# Main_Sheet_-_Comments.net
KiCad netlist of a schematic drawn in Altium Designer
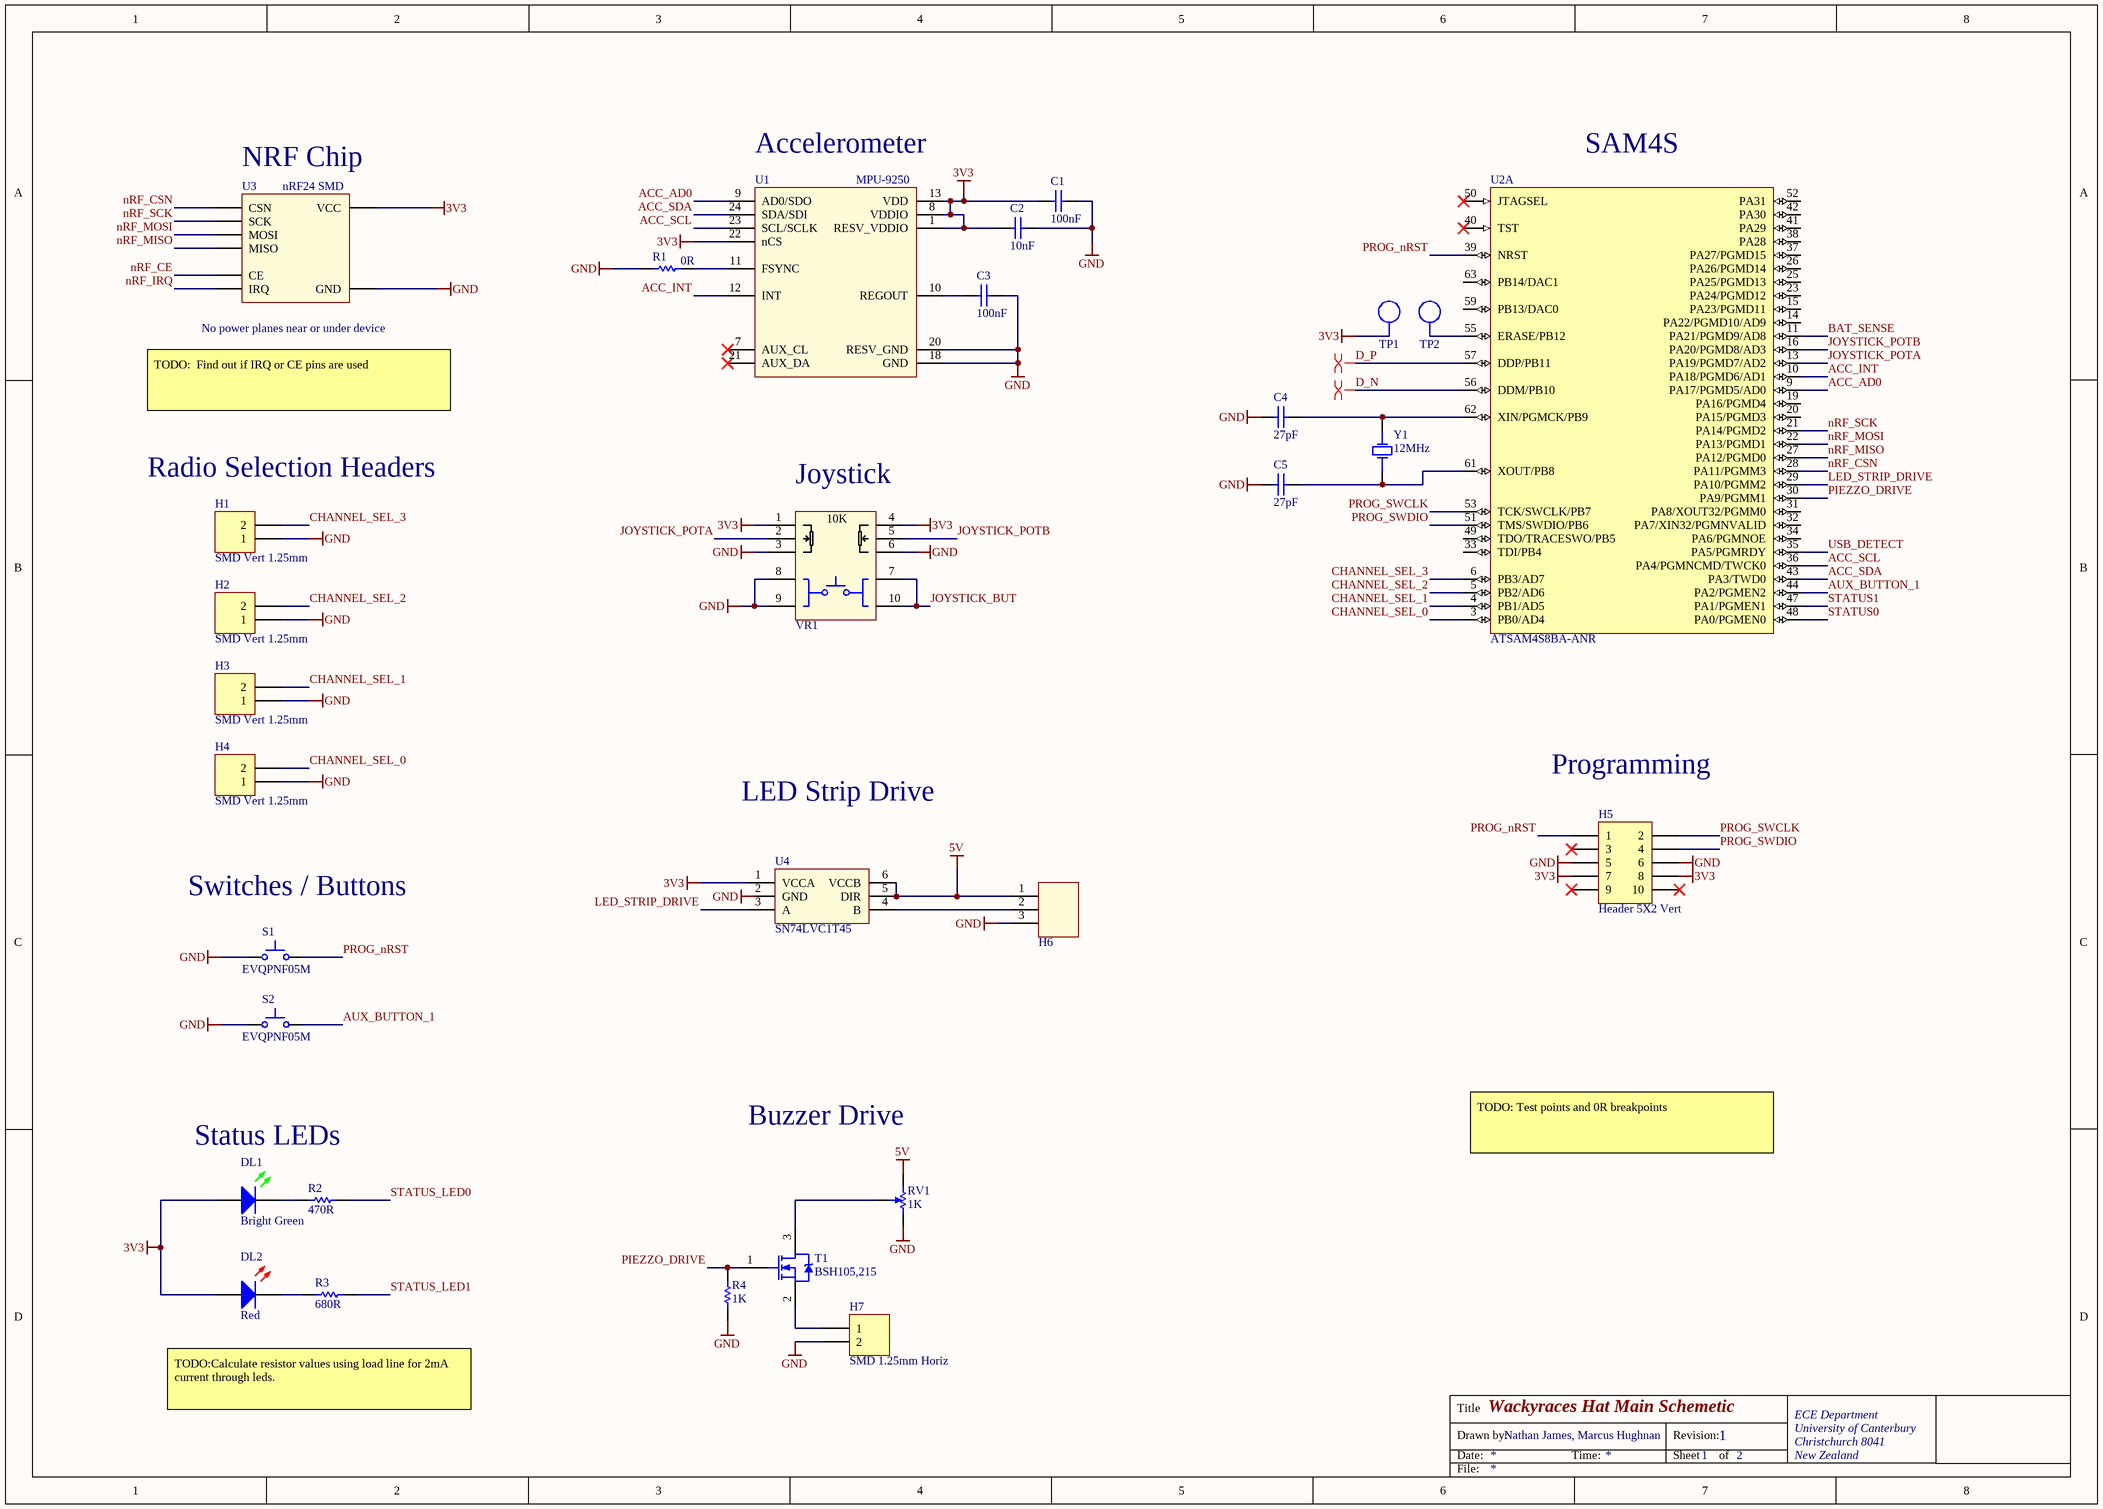
[diagram p0: Main Sheet - Comments.SchDoc]

(export (version "E")
  (design (tool "Eeschema 10.0.6"))
  (components
    (comp (ref "C1")
      (value "100nF")
      (footprint "CAPC1608L")
      (description "CAP CER 100nF X7R +-10% 50V 0603")
      (libsource (lib "ECE AD19Components_19V1") (part "CC_100nF_0603"))
    )
    (comp (ref "C2")
      (value "10nF")
      (footprint "CAPC1608L")
      (description "CAP CER 10nF X7R +-10% 50V 0603")
      (libsource (lib "ECE AD19Components_19V1") (part "CC_10nF_0603"))
    )
    (comp (ref "C3")
      (value "100nF")
      (footprint "CAPC1608L")
      (description "CAP CER 100nF X7R +-10% 50V 0603")
      (libsource (lib "ECE AD19Components_19V1") (part "CC_100nF_0603"))
    )
    (comp (ref "C4")
      (value "27pF")
      (footprint "CAPC1608L")
      (description "CAP CER 27pF NPO/COG +-5% 50V 0603")
      (libsource (lib "ECE AD19Components_19V1") (part "CC_27pF_0603"))
    )
    (comp (ref "C5")
      (value "27pF")
      (footprint "CAPC1608L")
      (description "CAP CER 27pF NPO/COG +-5% 50V 0603")
      (libsource (lib "ECE AD19Components_19V1") (part "CC_27pF_0603"))
    )
    (comp (ref "DL1")
      (value "Bright Green")
      (footprint "WL-SMCW0603")
      (description "LED Bright Green 40mcd 0603 SMD")
      (fields
        (field (name "MANUFACTURER") "WURTH ELEKTRONIK")
        (field (name "MANUFACTURER PART NUMBER") "150060VS75000")
        (field (name "LED COLOUR") "Bright Green")
      )
      (libsource (lib "ECE AD19Components_19V1") (part "DL_150060VS75000"))
    )
    (comp (ref "DL2")
      (value "Red")
      (footprint "WL-SMCW0603")
      (description "LED Red 250mcd 0603 SMD")
      (fields
        (field (name "MANUFACTURER") "WURTH ELEKTRONIK")
        (field (name "MANUFACTURER PART NUMBER") "150060RS75000")
        (field (name "LED COLOUR") "Red")
      )
      (libsource (lib "ECE AD19Components_19V1") (part "DL_150060RS75000"))
    )
    (comp (ref "H1")
      (value "SMD Vert 1.25mm")
      (footprint "SD-53398-0219")
      (description "Header_Vert_2Pos_1.25mm_125V@1A_SMT")
      (fields
        (field (name "MANUFACTURER") "Molex Inc")
        (field (name "MANUFACTURER PART NUMBER") "0533980271")
      )
      (libsource (lib "ECE AD19Components_19V1") (part "JB_53398-02"))
    )
    (comp (ref "H2")
      (value "SMD Vert 1.25mm")
      (footprint "SD-53398-0219")
      (description "Header_Vert_2Pos_1.25mm_125V@1A_SMT")
      (fields
        (field (name "MANUFACTURER") "Molex Inc")
        (field (name "MANUFACTURER PART NUMBER") "0533980271")
      )
      (libsource (lib "ECE AD19Components_19V1") (part "JB_53398-02"))
    )
    (comp (ref "H3")
      (value "SMD Vert 1.25mm")
      (footprint "SD-53398-0219")
      (description "Header_Vert_2Pos_1.25mm_125V@1A_SMT")
      (fields
        (field (name "MANUFACTURER") "Molex Inc")
        (field (name "MANUFACTURER PART NUMBER") "0533980271")
      )
      (libsource (lib "ECE AD19Components_19V1") (part "JB_53398-02"))
    )
    (comp (ref "H4")
      (value "SMD Vert 1.25mm")
      (footprint "SD-53398-0219")
      (description "Header_Vert_2Pos_1.25mm_125V@1A_SMT")
      (fields
        (field (name "MANUFACTURER") "Molex Inc")
        (field (name "MANUFACTURER PART NUMBER") "0533980271")
      )
      (libsource (lib "ECE AD19Components_19V1") (part "JB_53398-02"))
    )
    (comp (ref "H5")
      (value "Header 5X2 Vert")
      (footprint "IDC2.54-V10D")
      (description "IDC Header, 2,54mm, 10-Pin, Vert")
      (libsource (lib "ECE AD19Components_19V1") (part "JA_HDR_IDC_5X2_VERT"))
    )
    (comp (ref "H6")
      (value "HEADER_3")
      (footprint "HEADER_3POS")
      (description "3Pin Header 2.54mm spacing")
      (libsource (lib "ENCE461AD19_19V2") (part "HEADER_3"))
    )
    (comp (ref "H7")
      (value "SMD 1.25mm Horiz")
      (footprint "SD-53261-0219")
      (description "Header_Horiz_2Pos_1.25mm_125V@1A_SMT")
      (fields (field (name "MANUFACTURER") "MOLEX") (field (name "MANUFACTURER PART NUMBER") "53261-0271"))
      (libsource (lib "ECE AD19Components_19V1") (part "JB_53261-02"))
    )
    (comp (ref "R1")
      (value "0R")
      (footprint "RESC1608L")
      (description "RES 0.0 OHM 1/10W 5% 0603 SMD")
      (libsource (lib "ECE AD19Components_19V1") (part "RS_0R0"))
    )
    (comp (ref "R2")
      (value "470R")
      (footprint "RESC1608L")
      (description "RES 470 OHM 1/10W 5% 0603 SMD")
      (libsource (lib "ECE AD19Components_19V1") (part "RS_470R"))
    )
    (comp (ref "R3")
      (value "680R")
      (footprint "RESC3216L")
      (description "RES 680R OHM 1/4W 5% 1206 SMD")
      (libsource (lib "ECE AD19Components_19V1") (part "RT_680R"))
    )
    (comp (ref "R4")
      (value "1K")
      (footprint "RESC1608L")
      (description "RES 1.0K OHM 1/10W 5% 0603 SMD")
      (libsource (lib "ECE AD19Components_19V1") (part "RS_1K"))
    )
    (comp (ref "RV1")
      (value "1K")
      (footprint "PVZ2A")
      (description "Trim Pot SMD 1K Murata PVZ2 Series SMD")
      (fields
        (field (name "MANUFACTURER") "MURATA")
        (field (name "MANUFACTURER PART NUMBER") "PVZ2A102C04B00")
      )
      (libsource (lib "ECE AD19Components_19V1") (part "RM_1K"))
    )
    (comp (ref "S1")
      (value "EVQPNF05M")
      (footprint "EVQPNF05M")
      (description "Panasonic 6 x 3.5mm SMD Light Touch Switch Type SMD")
      (fields (field (name "MANUFACTURER") "Panasonic"))
      (libsource (lib "ECE AD19Components_19V1") (part "WS_EVQPNF05M"))
    )
    (comp (ref "S2")
      (value "EVQPNF05M")
      (footprint "EVQPNF05M")
      (description "Panasonic 6 x 3.5mm SMD Light Touch Switch Type SMD")
      (fields (field (name "MANUFACTURER") "Panasonic"))
      (libsource (lib "ECE AD19Components_19V1") (part "WS_EVQPNF05M"))
    )
    (comp (ref "T1")
      (value "BSH105,215")
      (footprint "SOT23_L")
      (description "MOSFET N-CH 20V 1.05A SOT-23")
      (fields
        (field (name "MANUFACTURER") "NXP Semiconductors")
        (field (name "MANUFACTURER PART NUMBER") "BSH105,215")
      )
      (libsource (lib "ECE AD19Components_19V1") (part "TM_BSH105"))
    )
    (comp (ref "TP1")
      (value "Erase")
      (footprint "TP_1206")
      (description "Test-Point 3.3x1.6x2.1mm SMD")
      (fields
        (field (name "MANUFACTURER") "Harwin Inc")
        (field (name "MANUFACTURER PART NUMBER") "S1751-46R")
      )
      (libsource (lib "ECE AD19Components_19V1") (part "TP_1206"))
    )
    (comp (ref "TP2")
      (value "Erase")
      (footprint "TP_1206")
      (description "Test-Point 3.3x1.6x2.1mm SMD")
      (fields
        (field (name "MANUFACTURER") "Harwin Inc")
        (field (name "MANUFACTURER PART NUMBER") "S1751-46R")
      )
      (libsource (lib "ECE AD19Components_19V1") (part "TP_1206"))
    )
    (comp (ref "U1")
      (value "MPU-9250")
      (footprint "Quad24")
      (description "9 axis IMU")
      (libsource (lib "ENCE461AD19_19V2") (part "MPU-9250"))
    )
    (comp (ref "U2")
      (value "ATSAM4S8BA-ANR")
      (footprint "LQFP64_L")
      (description "IC MCU 32BIT 512KB FLASH 64LQFP")
      (fields (field (name "MANUFACTURER") "Atmel"))
      (libsource (lib "ECE AD19Components_19V1") (part "SE_ATSAM4S16BA-MU"))
    )
    (comp (ref "U3")
      (value "nRF24 SMD")
      (footprint "NRF24")
      (description "nRF24 SMD Module")
      (fields (field (name "WARNING") "No power planes near or under device"))
      (libsource (lib "ENCE461AD19_19V2") (part "NRF24"))
    )
    (comp (ref "U4")
      (value "SN74LVC1T45")
      (footprint "SOT23-6_N")
      (description "1.8V - 5V level converter")
      (libsource (lib "ENCE461_extras_2020") (part "SN74LVC1T45"))
    )
    (comp (ref "VR1")
      (value "Joystick 10k with Sw")
      (footprint "Joystick_Sw")
      (description "JOYSTICK 10K OHM 2 AXIS TH")
      (libsource (lib "ENCE461AD19_19V2") (part "Joystick 10k with Sw"))
    )
    (comp (ref "Y1")
      (value "12MHz")
      (footprint "6.0X3.5-4")
      (description "CRYSTAL 12MHZ 18PF 6X3.5mm SMD")
      (fields
        (field (name "MANUFACTURER") "CTS-Frequency Controls")
        (field (name "MANUFACTURER PART NUMBER") "406C35D12M00000")
        (field (name "FREQUENCY") "12MHz")
      )
      (libsource (lib "ECE AD19Components_19V1") (part "XT_CRYSTAL_12MHz_18pF"))
    )
  )
  (nets
    (net (code "1") (name "/ACC_AD0") (class "Default")
      (node (ref "U1") (pin "9") (pinfunction "AD0/SDO_9") (pintype "passive"))
      (node (ref "U2") (pin "9") (pinfunction "PA17/PGMD5/AD0_9") (pintype "bidirectional"))
    )
    (net (code "2") (name "/ACC_INT") (class "Default")
      (node (ref "U1") (pin "12") (pinfunction "INT_12") (pintype "passive"))
      (node (ref "U2") (pin "10") (pinfunction "PA18/PGMD6/AD1_10") (pintype "bidirectional"))
    )
    (net (code "3") (name "/ACC_SCL") (class "Default")
      (node (ref "U1") (pin "23") (pinfunction "SCL/SCLK_23") (pintype "passive"))
      (node (ref "U2") (pin "36") (pinfunction "PA4/PGMNCMD/TWCK0_36") (pintype "bidirectional"))
    )
    (net (code "4") (name "/ACC_SDA") (class "Default")
      (node (ref "U1") (pin "24") (pinfunction "SDA/SDI_24") (pintype "passive"))
      (node (ref "U2") (pin "43") (pinfunction "PA3/TWD0_43") (pintype "bidirectional"))
    )
    (net (code "5") (name "/AUX_BUTTON_1") (class "Default")
      (node (ref "S2") (pin "2") (pintype "passive"))
      (node (ref "U2") (pin "44") (pinfunction "PA2/PGMEN2_44") (pintype "bidirectional"))
    )
    (net (code "6") (name "/BAT_SENSE") (class "Default")
      (node (ref "U2") (pin "11") (pinfunction "PA21/PGMD9/AD8_11") (pintype "bidirectional"))
    )
    (net (code "7") (name "/CHANNEL_SEL_0") (class "Default")
      (node (ref "H4") (pin "2") (pinfunction "2_2") (pintype "passive"))
      (node (ref "U2") (pin "3") (pinfunction "PB0/AD4_3") (pintype "bidirectional"))
    )
    (net (code "8") (name "/CHANNEL_SEL_1") (class "Default")
      (node (ref "H3") (pin "2") (pinfunction "2_2") (pintype "passive"))
      (node (ref "U2") (pin "4") (pinfunction "PB1/AD5_4") (pintype "bidirectional"))
    )
    (net (code "9") (name "/CHANNEL_SEL_2") (class "Default")
      (node (ref "H2") (pin "2") (pinfunction "2_2") (pintype "passive"))
      (node (ref "U2") (pin "5") (pinfunction "PB2/AD6_5") (pintype "bidirectional"))
    )
    (net (code "10") (name "/CHANNEL_SEL_3") (class "Default")
      (node (ref "H1") (pin "2") (pinfunction "2_2") (pintype "passive"))
      (node (ref "U2") (pin "6") (pinfunction "PB3/AD7_6") (pintype "bidirectional"))
    )
    (net (code "11") (name "/D_N") (class "Default")
      (node (ref "U2") (pin "56") (pinfunction "DDM/PB10_56") (pintype "bidirectional"))
    )
    (net (code "12") (name "/D_P") (class "Default")
      (node (ref "U2") (pin "57") (pinfunction "DDP/PB11_57") (pintype "bidirectional"))
    )
    (net (code "13") (name "/JOYSTICK_BUT") (class "Default")
      (node (ref "VR1") (pin "10") (pinfunction "10_10") (pintype "passive"))
      (node (ref "VR1") (pin "7") (pinfunction "7_7") (pintype "passive"))
    )
    (net (code "14") (name "/JOYSTICK_POTA") (class "Default")
      (node (ref "U2") (pin "13") (pinfunction "PA19/PGMD7/AD2_13") (pintype "bidirectional"))
      (node (ref "VR1") (pin "2") (pinfunction "2_2") (pintype "passive"))
    )
    (net (code "15") (name "/JOYSTICK_POTB") (class "Default")
      (node (ref "U2") (pin "16") (pinfunction "PA20/PGMD8/AD3_16") (pintype "bidirectional"))
      (node (ref "VR1") (pin "5") (pinfunction "2'_5") (pintype "passive"))
    )
    (net (code "16") (name "/LED_STRIP_DRIVE") (class "Default")
      (node (ref "U2") (pin "29") (pinfunction "PA10/PGMM2_29") (pintype "bidirectional"))
      (node (ref "U4") (pin "3") (pinfunction "A_3") (pintype "passive"))
    )
    (net (code "17") (name "/PIEZZO_DRIVE") (class "Default")
      (node (ref "R4") (pin "2") (pinfunction "2_2") (pintype "passive"))
      (node (ref "T1") (pin "1") (pinfunction "1_1") (pintype "passive"))
      (node (ref "U2") (pin "30") (pinfunction "PA9/PGMM1_30") (pintype "bidirectional"))
    )
    (net (code "18") (name "/PROG_SWCLK") (class "Default")
      (node (ref "H5") (pin "2") (pinfunction "2_2") (pintype "passive"))
      (node (ref "U2") (pin "53") (pinfunction "TCK/SWCLK/PB7_53") (pintype "bidirectional"))
    )
    (net (code "19") (name "/PROG_SWDIO") (class "Default")
      (node (ref "H5") (pin "4") (pinfunction "4_4") (pintype "passive"))
      (node (ref "U2") (pin "51") (pinfunction "TMS/SWDIO/PB6_51") (pintype "bidirectional"))
    )
    (net (code "20") (name "/PROG_nRST") (class "Default")
      (node (ref "H5") (pin "1") (pinfunction "1_1") (pintype "passive"))
      (node (ref "S1") (pin "2") (pintype "passive"))
      (node (ref "U2") (pin "39") (pinfunction "NRST_39") (pintype "bidirectional"))
    )
    (net (code "21") (name "/STATUS0") (class "Default")
      (node (ref "U2") (pin "48") (pinfunction "PA0/PGMEN0_48") (pintype "bidirectional"))
    )
    (net (code "22") (name "/STATUS1") (class "Default")
      (node (ref "U2") (pin "47") (pinfunction "PA1/PGMEN1_47") (pintype "bidirectional"))
    )
    (net (code "23") (name "/STATUS_LED0") (class "Default")
      (node (ref "R2") (pin "2") (pinfunction "2_2") (pintype "passive"))
    )
    (net (code "24") (name "/STATUS_LED1") (class "Default")
      (node (ref "R3") (pin "2") (pinfunction "2_2") (pintype "passive"))
    )
    (net (code "25") (name "/USB_DETECT") (class "Default")
      (node (ref "U2") (pin "35") (pinfunction "PA5/PGMRDY_35") (pintype "bidirectional"))
    )
    (net (code "26") (name "/nRF_CE") (class "Default")
      (node (ref "U3") (pin "3") (pinfunction "CE_3") (pintype "passive"))
    )
    (net (code "27") (name "/nRF_CSN") (class "Default")
      (node (ref "U2") (pin "28") (pinfunction "PA11/PGMM3_28") (pintype "bidirectional"))
      (node (ref "U3") (pin "4") (pinfunction "CSN_4") (pintype "passive"))
    )
    (net (code "28") (name "/nRF_IRQ") (class "Default")
      (node (ref "U3") (pin "8") (pinfunction "IRQ_8") (pintype "passive"))
    )
    (net (code "29") (name "/nRF_MISO") (class "Default")
      (node (ref "U2") (pin "27") (pinfunction "PA12/PGMD0_27") (pintype "bidirectional"))
      (node (ref "U3") (pin "7") (pinfunction "MISO_7") (pintype "passive"))
    )
    (net (code "30") (name "/nRF_MOSI") (class "Default")
      (node (ref "U2") (pin "22") (pinfunction "PA13/PGMD1_22") (pintype "bidirectional"))
      (node (ref "U3") (pin "6") (pinfunction "MOSI_6") (pintype "passive"))
    )
    (net (code "31") (name "/nRF_SCK") (class "Default")
      (node (ref "U2") (pin "21") (pinfunction "PA14/PGMD2_21") (pintype "bidirectional"))
      (node (ref "U3") (pin "5") (pinfunction "SCK_5") (pintype "passive"))
    )
    (net (code "32") (name "3V3") (class "Default")
      (node (ref "C1") (pin "1") (pinfunction "1_1") (pintype "passive"))
      (node (ref "C2") (pin "1") (pinfunction "1_1") (pintype "passive"))
      (node (ref "DL1") (pin "2") (pinfunction "A_2") (pintype "passive"))
      (node (ref "DL2") (pin "2") (pinfunction "A_2") (pintype "passive"))
      (node (ref "H5") (pin "7") (pinfunction "7_7") (pintype "passive"))
      (node (ref "H5") (pin "8") (pinfunction "8_8") (pintype "passive"))
      (node (ref "TP1") (pin "1") (pinfunction "1_1") (pintype "passive"))
      (node (ref "U1") (pin "1") (pinfunction "RESV_VDDIO_1") (pintype "passive"))
      (node (ref "U1") (pin "13") (pinfunction "VDD_13") (pintype "passive"))
      (node (ref "U1") (pin "22") (pinfunction "nCS_22") (pintype "passive"))
      (node (ref "U1") (pin "8") (pinfunction "VDDIO_8") (pintype "passive"))
      (node (ref "U3") (pin "1") (pinfunction "VCC_1") (pintype "passive"))
      (node (ref "U4") (pin "1") (pinfunction "VCCA_1") (pintype "passive"))
      (node (ref "VR1") (pin "1") (pinfunction "1_1") (pintype "passive"))
      (node (ref "VR1") (pin "4") (pinfunction "1'_4") (pintype "passive"))
    )
    (net (code "33") (name "5V") (class "Default")
      (node (ref "H6") (pin "1") (pintype "passive"))
      (node (ref "RV1") (pin "3") (pinfunction "-_3") (pintype "passive"))
      (node (ref "U4") (pin "5") (pinfunction "DIR_5") (pintype "passive"))
      (node (ref "U4") (pin "6") (pinfunction "VCCB_6") (pintype "passive"))
    )
    (net (code "34") (name "GND") (class "Default")
      (node (ref "C1") (pin "2") (pinfunction "2_2") (pintype "passive"))
      (node (ref "C2") (pin "2") (pinfunction "2_2") (pintype "passive"))
      (node (ref "C3") (pin "2") (pinfunction "2_2") (pintype "passive"))
      (node (ref "C4") (pin "1") (pinfunction "1_1") (pintype "passive"))
      (node (ref "C5") (pin "1") (pinfunction "1_1") (pintype "passive"))
      (node (ref "H1") (pin "1") (pinfunction "1_1") (pintype "passive"))
      (node (ref "H2") (pin "1") (pinfunction "1_1") (pintype "passive"))
      (node (ref "H3") (pin "1") (pinfunction "1_1") (pintype "passive"))
      (node (ref "H4") (pin "1") (pinfunction "1_1") (pintype "passive"))
      (node (ref "H5") (pin "5") (pinfunction "5_5") (pintype "passive"))
      (node (ref "H5") (pin "6") (pinfunction "6_6") (pintype "passive"))
      (node (ref "H6") (pin "3") (pintype "passive"))
      (node (ref "H7") (pin "2") (pinfunction "2_2") (pintype "passive"))
      (node (ref "R1") (pin "1") (pinfunction "1_1") (pintype "passive"))
      (node (ref "R4") (pin "1") (pinfunction "1_1") (pintype "passive"))
      (node (ref "RV1") (pin "1") (pinfunction "1_1") (pintype "passive"))
      (node (ref "S1") (pin "1") (pintype "passive"))
      (node (ref "S2") (pin "1") (pintype "passive"))
      (node (ref "U1") (pin "18") (pinfunction "GND_18") (pintype "passive"))
      (node (ref "U1") (pin "20") (pinfunction "RESV_GND_20") (pintype "passive"))
      (node (ref "U3") (pin "2") (pinfunction "GND_2") (pintype "passive"))
      (node (ref "VR1") (pin "3") (pinfunction "3_3") (pintype "passive"))
      (node (ref "VR1") (pin "6") (pinfunction "3'_6") (pintype "passive"))
      (node (ref "VR1") (pin "8") (pinfunction "8_8") (pintype "passive"))
      (node (ref "VR1") (pin "9") (pinfunction "9_9") (pintype "passive"))
    )
    (net (code "35") (name "Net-(DL1-K)") (class "Default")
      (node (ref "DL1") (pin "1") (pinfunction "K_1") (pintype "passive"))
      (node (ref "R2") (pin "1") (pinfunction "1_1") (pintype "passive"))
    )
    (net (code "36") (name "Net-(DL2-K)") (class "Default")
      (node (ref "DL2") (pin "1") (pinfunction "K_1") (pintype "passive"))
      (node (ref "R3") (pin "1") (pinfunction "1_1") (pintype "passive"))
    )
    (net (code "37") (name "Net-(H7-Pad1)") (class "Default")
      (node (ref "H7") (pin "1") (pinfunction "1_1") (pintype "passive"))
      (node (ref "T1") (pin "2") (pinfunction "2_2") (pintype "passive"))
    )
    (net (code "38") (name "Net-(RV1-W)") (class "Default")
      (node (ref "RV1") (pin "2") (pinfunction "W_2") (pintype "passive"))
      (node (ref "T1") (pin "3") (pinfunction "3_3") (pintype "passive"))
    )
    (net (code "39") (name "Net-(U1-FSYNC)") (class "Default")
      (node (ref "R1") (pin "2") (pinfunction "2_2") (pintype "passive"))
      (node (ref "U1") (pin "11") (pinfunction "FSYNC_11") (pintype "passive"))
    )
    (net (code "40") (name "Net-(U1-REGOUT)") (class "Default")
      (node (ref "C3") (pin "1") (pinfunction "1_1") (pintype "passive"))
      (node (ref "U1") (pin "10") (pinfunction "REGOUT_10") (pintype "passive"))
    )
    (net (code "41") (name "Net-(U2A-ERASE{slash}PB12)") (class "Default")
      (node (ref "TP2") (pin "1") (pinfunction "1_1") (pintype "passive"))
      (node (ref "U2") (pin "55") (pinfunction "ERASE/PB12_55") (pintype "bidirectional"))
    )
    (net (code "42") (name "Net-(U2A-XIN{slash}PGMCK{slash}PB9)") (class "Default")
      (node (ref "C4") (pin "2") (pinfunction "2_2") (pintype "passive"))
      (node (ref "U2") (pin "62") (pinfunction "XIN/PGMCK/PB9_62") (pintype "bidirectional"))
      (node (ref "Y1") (pin "3") (pinfunction "OSC2_3") (pintype "passive"))
    )
    (net (code "43") (name "Net-(U2A-XOUT{slash}PB8)") (class "Default")
      (node (ref "C5") (pin "2") (pinfunction "2_2") (pintype "passive"))
      (node (ref "U2") (pin "61") (pinfunction "XOUT/PB8_61") (pintype "bidirectional"))
      (node (ref "Y1") (pin "1") (pinfunction "OSC1_1") (pintype "passive"))
    )
    (net (code "44") (name "Net-(U4-B)") (class "Default")
      (node (ref "H6") (pin "2") (pintype "passive"))
      (node (ref "U4") (pin "4") (pinfunction "B_4") (pintype "passive"))
    )
    (net (code "45") (name "unconnected-(H5-Pad3)") (class "Default")
      (node (ref "H5") (pin "3") (pinfunction "3_3") (pintype "passive+no_connect"))
    )
    (net (code "46") (name "unconnected-(H5-Pad9)") (class "Default")
      (node (ref "H5") (pin "9") (pinfunction "9_9") (pintype "passive+no_connect"))
    )
    (net (code "47") (name "unconnected-(H5-Pad10)") (class "Default")
      (node (ref "H5") (pin "10") (pinfunction "10_10") (pintype "passive+no_connect"))
    )
    (net (code "48") (name "unconnected-(U1-AUX_CL-Pad7)") (class "Default")
      (node (ref "U1") (pin "7") (pinfunction "AUX_CL_7") (pintype "passive+no_connect"))
    )
    (net (code "49") (name "unconnected-(U1-AUX_DA-Pad21)") (class "Default")
      (node (ref "U1") (pin "21") (pinfunction "AUX_DA_21") (pintype "passive+no_connect"))
    )
    (net (code "50") (name "unconnected-(U2A-JTAGSEL-Pad50)") (class "Default")
      (node (ref "U2") (pin "50") (pinfunction "JTAGSEL_50") (pintype "input+no_connect"))
    )
    (net (code "51") (name "unconnected-(U2A-PA6{slash}PGMNOE-Pad34)") (class "Default")
      (node (ref "U2") (pin "34") (pinfunction "PA6/PGMNOE_34") (pintype "bidirectional"))
    )
    (net (code "52") (name "unconnected-(U2A-PA7{slash}XIN32{slash}PGMNVALID-Pad32)") (class "Default")
      (node (ref "U2") (pin "32") (pinfunction "PA7/XIN32/PGMNVALID_32") (pintype "bidirectional"))
    )
    (net (code "53") (name "unconnected-(U2A-PA8{slash}XOUT32{slash}PGMM0-Pad31)") (class "Default")
      (node (ref "U2") (pin "31") (pinfunction "PA8/XOUT32/PGMM0_31") (pintype "bidirectional"))
    )
    (net (code "54") (name "unconnected-(U2A-PA15{slash}PGMD3-Pad20)") (class "Default")
      (node (ref "U2") (pin "20") (pinfunction "PA15/PGMD3_20") (pintype "bidirectional"))
    )
    (net (code "55") (name "unconnected-(U2A-PA16{slash}PGMD4-Pad19)") (class "Default")
      (node (ref "U2") (pin "19") (pinfunction "PA16/PGMD4_19") (pintype "bidirectional"))
    )
    (net (code "56") (name "unconnected-(U2A-PA22{slash}PGMD10{slash}AD9-Pad14)") (class "Default")
      (node (ref "U2") (pin "14") (pinfunction "PA22/PGMD10/AD9_14") (pintype "bidirectional"))
    )
    (net (code "57") (name "unconnected-(U2A-PA23{slash}PGMD11-Pad15)") (class "Default")
      (node (ref "U2") (pin "15") (pinfunction "PA23/PGMD11_15") (pintype "bidirectional"))
    )
    (net (code "58") (name "unconnected-(U2A-PA24{slash}PGMD12-Pad23)") (class "Default")
      (node (ref "U2") (pin "23") (pinfunction "PA24/PGMD12_23") (pintype "bidirectional"))
    )
    (net (code "59") (name "unconnected-(U2A-PA25{slash}PGMD13-Pad25)") (class "Default")
      (node (ref "U2") (pin "25") (pinfunction "PA25/PGMD13_25") (pintype "bidirectional"))
    )
    (net (code "60") (name "unconnected-(U2A-PA26{slash}PGMD14-Pad26)") (class "Default")
      (node (ref "U2") (pin "26") (pinfunction "PA26/PGMD14_26") (pintype "bidirectional"))
    )
    (net (code "61") (name "unconnected-(U2A-PA27{slash}PGMD15-Pad37)") (class "Default")
      (node (ref "U2") (pin "37") (pinfunction "PA27/PGMD15_37") (pintype "bidirectional"))
    )
    (net (code "62") (name "unconnected-(U2A-PA28-Pad38)") (class "Default")
      (node (ref "U2") (pin "38") (pinfunction "PA28_38") (pintype "bidirectional"))
    )
    (net (code "63") (name "unconnected-(U2A-PA29-Pad41)") (class "Default")
      (node (ref "U2") (pin "41") (pinfunction "PA29_41") (pintype "bidirectional"))
    )
    (net (code "64") (name "unconnected-(U2A-PA30-Pad42)") (class "Default")
      (node (ref "U2") (pin "42") (pinfunction "PA30_42") (pintype "bidirectional"))
    )
    (net (code "65") (name "unconnected-(U2A-PA31-Pad52)") (class "Default")
      (node (ref "U2") (pin "52") (pinfunction "PA31_52") (pintype "bidirectional"))
    )
    (net (code "66") (name "unconnected-(U2A-PB13{slash}DAC0-Pad59)") (class "Default")
      (node (ref "U2") (pin "59") (pinfunction "PB13/DAC0_59") (pintype "bidirectional"))
    )
    (net (code "67") (name "unconnected-(U2A-PB14{slash}DAC1-Pad63)") (class "Default")
      (node (ref "U2") (pin "63") (pinfunction "PB14/DAC1_63") (pintype "bidirectional"))
    )
    (net (code "68") (name "unconnected-(U2A-TDI{slash}PB4-Pad33)") (class "Default")
      (node (ref "U2") (pin "33") (pinfunction "TDI/PB4_33") (pintype "bidirectional"))
    )
    (net (code "69") (name "unconnected-(U2A-TDO{slash}TRACESWO{slash}PB5-Pad49)") (class "Default")
      (node (ref "U2") (pin "49") (pinfunction "TDO/TRACESWO/PB5_49") (pintype "bidirectional"))
    )
    (net (code "70") (name "unconnected-(U2A-TST-Pad40)") (class "Default")
      (node (ref "U2") (pin "40") (pinfunction "TST_40") (pintype "input+no_connect"))
    )
    (net (code "71") (name "unconnected-(U4-GND-Pad2)") (class "Default")
      (node (ref "U4") (pin "2") (pinfunction "GND_2") (pintype "passive"))
    )
  )
)
